# i2c-breakout.net
KiCad netlist of a schematic drawn in EAGLE
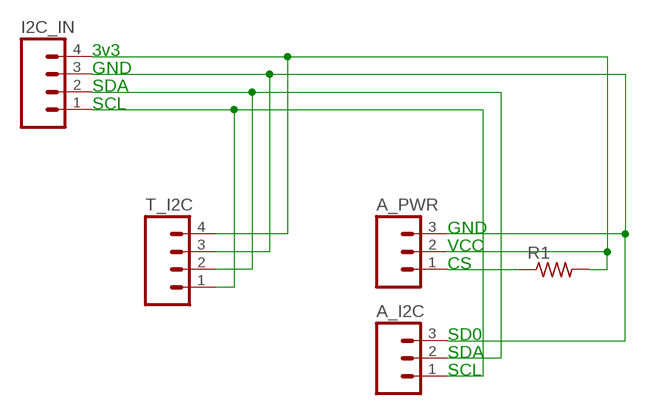
[diagram p0: schematic, sheet 1]

(export (version "E")
  (design (tool "Eeschema 10.0.6"))
  (components
    (comp (ref "A_I2C")
      (value "M03PTH")
      (footprint "eagle-import:1X03")
      (libsource (lib "eagle-import") (part "M03PTH"))
    )
    (comp (ref "A_PWR")
      (value "M03PTH")
      (footprint "eagle-import:1X03")
      (libsource (lib "eagle-import") (part "M03PTH"))
    )
    (comp (ref "I2C_IN")
      (value "M04PTH")
      (footprint "eagle-import:1X04")
      (libsource (lib "eagle-import") (part "M04PTH"))
    )
    (comp (ref "R1")
      (value "R-US_0207/7")
      (footprint "eagle-import:0207_7")
      (libsource (lib "eagle-import") (part "R-US_0207/7"))
    )
    (comp (ref "T_I2C")
      (value "M04PTH")
      (footprint "eagle-import:1X04")
      (libsource (lib "eagle-import") (part "M04PTH"))
    )
  )
  (nets
    (net (code "1") (name "Net-(A_I2C-Pad1)") (class "Default")
      (node (ref "A_I2C") (pin "1") (pinfunction "1_1") (pintype "passive"))
      (node (ref "I2C_IN") (pin "1") (pinfunction "1_1") (pintype "passive"))
      (node (ref "T_I2C") (pin "1") (pinfunction "1_1") (pintype "passive"))
    )
    (net (code "2") (name "Net-(A_I2C-Pad2)") (class "Default")
      (node (ref "A_I2C") (pin "2") (pinfunction "2_2") (pintype "passive"))
      (node (ref "I2C_IN") (pin "2") (pinfunction "2_2") (pintype "passive"))
      (node (ref "T_I2C") (pin "2") (pinfunction "2_2") (pintype "passive"))
    )
    (net (code "3") (name "Net-(A_I2C-Pad3)") (class "Default")
      (node (ref "A_I2C") (pin "3") (pinfunction "3_3") (pintype "passive"))
      (node (ref "A_PWR") (pin "3") (pinfunction "3_3") (pintype "passive"))
      (node (ref "I2C_IN") (pin "3") (pinfunction "3_3") (pintype "passive"))
      (node (ref "T_I2C") (pin "3") (pinfunction "3_3") (pintype "passive"))
    )
    (net (code "4") (name "Net-(A_PWR-Pad1)") (class "Default")
      (node (ref "A_PWR") (pin "1") (pinfunction "1_1") (pintype "passive"))
      (node (ref "R1") (pin "1") (pinfunction "1_1") (pintype "passive"))
    )
    (net (code "5") (name "Net-(A_PWR-Pad2)") (class "Default")
      (node (ref "A_PWR") (pin "2") (pinfunction "2_2") (pintype "passive"))
      (node (ref "I2C_IN") (pin "4") (pinfunction "4_4") (pintype "passive"))
      (node (ref "R1") (pin "2") (pinfunction "2_2") (pintype "passive"))
      (node (ref "T_I2C") (pin "4") (pinfunction "4_4") (pintype "passive"))
    )
  )
)
